# ATMEGA2560.net
KiCad netlist of a schematic drawn in Altium Designer
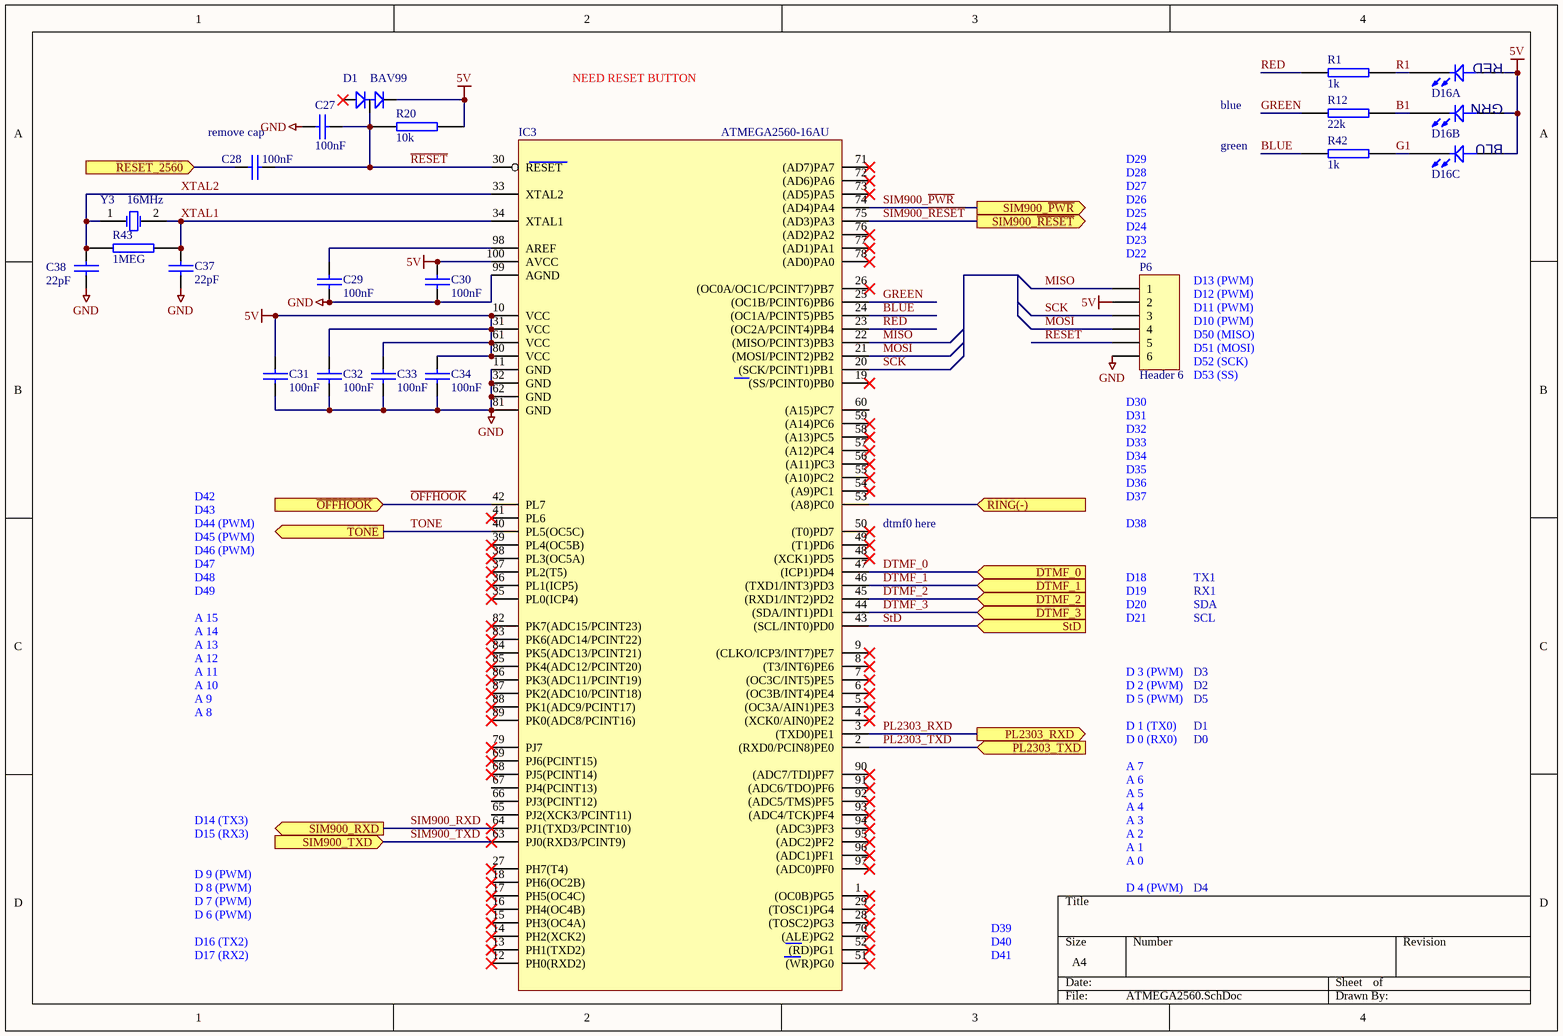
[diagram p0: ATMEGA2560.SchDoc]

(export (version "E")
  (design (tool "Eeschema 10.0.6"))
  (components
    (comp (ref "C27")
      (value "100nF")
      (footprint "CAP (3D) - 0603")
      (description "CAPACITOR SMD 0603")
      (fields (field (name "MOUSER PART NO.") "81-GCM188R71C104KA7D") (field (name "MANUFACTURER") "Murata"))
      (libsource (lib "NASCO Capacitors") (part "CAP SMD 0603 100nF"))
    )
    (comp (ref "C28")
      (value "100nF")
      (footprint "CAP (3D) - 0603")
      (description "CAPACITOR SMD 0603")
      (fields (field (name "MOUSER PART NO.") "81-GCM188R71C104KA7D") (field (name "MANUFACTURER") "Murata"))
      (libsource (lib "NASCO Capacitors") (part "CAP SMD 0603 100nF"))
    )
    (comp (ref "C29")
      (value "100nF")
      (footprint "CAP (3D) - 0603")
      (description "CAPACITOR SMD 0603")
      (fields (field (name "MOUSER PART NO.") "81-GCM188R71C104KA7D") (field (name "MANUFACTURER") "Murata"))
      (libsource (lib "NASCO Capacitors") (part "CAP SMD 0603 100nF"))
    )
    (comp (ref "C30")
      (value "100nF")
      (footprint "CAP (3D) - 0603")
      (description "CAPACITOR SMD 0603")
      (fields (field (name "MOUSER PART NO.") "81-GCM188R71C104KA7D") (field (name "MANUFACTURER") "Murata"))
      (libsource (lib "NASCO Capacitors") (part "CAP SMD 0603 100nF"))
    )
    (comp (ref "C31")
      (value "100nF")
      (footprint "CAP (3D) - 0603")
      (description "CAPACITOR SMD 0603")
      (fields (field (name "MOUSER PART NO.") "81-GCM188R71C104KA7D") (field (name "MANUFACTURER") "Murata"))
      (libsource (lib "NASCO Capacitors") (part "CAP SMD 0603 100nF"))
    )
    (comp (ref "C32")
      (value "100nF")
      (footprint "CAP (3D) - 0603")
      (description "CAPACITOR SMD 0603")
      (fields (field (name "MOUSER PART NO.") "81-GCM188R71C104KA7D") (field (name "MANUFACTURER") "Murata"))
      (libsource (lib "NASCO Capacitors") (part "CAP SMD 0603 100nF"))
    )
    (comp (ref "C33")
      (value "100nF")
      (footprint "CAP (3D) - 0603")
      (description "CAPACITOR SMD 0603")
      (fields (field (name "MOUSER PART NO.") "81-GCM188R71C104KA7D") (field (name "MANUFACTURER") "Murata"))
      (libsource (lib "NASCO Capacitors") (part "CAP SMD 0603 100nF"))
    )
    (comp (ref "C34")
      (value "100nF")
      (footprint "CAP (3D) - 0603")
      (description "CAPACITOR SMD 0603")
      (fields (field (name "MOUSER PART NO.") "81-GCM188R71C104KA7D") (field (name "MANUFACTURER") "Murata"))
      (libsource (lib "NASCO Capacitors") (part "CAP SMD 0603 100nF"))
    )
    (comp (ref "C37")
      (value "22pF")
      (footprint "CAP (3D) - 0603")
      (description "CAPACITOR SMD 0603")
      (fields
        (field (name "MANUFACTURER") "Vishay")
        (field (name "MANUFACTURER PART NO.") "VJ0603A220JXACW1BC")
      )
      (libsource (lib "NASCO Capacitors") (part "CAP SMD 0603 1nF"))
    )
    (comp (ref "C38")
      (value "22pF")
      (footprint "CAP (3D) - 0603")
      (description "CAPACITOR SMD 0603")
      (fields
        (field (name "MANUFACTURER") "Vishay")
        (field (name "MANUFACTURER PART NO.") "VJ0603A220JXACW1BC")
      )
      (libsource (lib "NASCO Capacitors") (part "CAP SMD 0603 1nF"))
    )
    (comp (ref "D1")
      (value "BAV99")
      (footprint "SOT23-3L")
      (description "DUAL DIODE, BAV99")
      (fields
        (field (name "MOUSER PART NO.") "771-BAV99/T3")
        (field (name "MANUFACTURER") "FAIRCHILD SEMICONDUCTOR")
      )
      (libsource (lib "NASCO") (part "BAV99"))
    )
    (comp (ref "D16")
      (value "RGB 5mm")
      (footprint "LED(3D) 5MM RIGHT ANGLE (RGB) - COMMON ANODE")
      (libsource (lib "NASCO") (part "RGB_5mm"))
    )
    (comp (ref "IC3")
      (value "ATMEGA2560-16AU")
      (footprint "TQFP100")
      (fields
        (field (name "MANUFACTURER") "Atmel")
        (field (name "MANUFACTURER PART NO.") "ATmega2560-16AU")
        (field (name "MOUSER PART NO.") "556-ATMEGA2560-16AU")
      )
      (libsource (lib "NASCO") (part "ATMEGA25602560-16AU"))
    )
    (comp (ref "P6")
      (value "Header 6")
      (footprint "HDR2X3 (3D)")
      (description "Header, 6-Pin")
      (libsource (lib "Miscellaneous Connectors") (part "Header 6"))
    )
    (comp (ref "R1")
      (value "1k")
      (footprint "RES (3D) - 0603")
      (description "RESISTOR SMD 0603")
      (fields (field (name "MOUSER PART NO.") "652-CR0603-JW-102ELF") (field (name "MANUFACTURER") "Bourns"))
      (libsource (lib "NASCO Resistors") (part "RES SMD 0603 10k"))
    )
    (comp (ref "R12")
      (value "22k")
      (footprint "RES (3D) - 0603")
      (description "RESISTOR SMD 0603")
      (fields (field (name "MOUSER PART NO.") "652-CR0603FX-4223ELF") (field (name "MANUFACTURER") "Bourns"))
      (libsource (lib "NASCO Resistors") (part "RES SMD 0603 10k"))
    )
    (comp (ref "R20")
      (value "10k")
      (footprint "RES (3D) - 0603")
      (description "RESISTOR SMD 0603 10k")
      (fields (field (name "MOUSER PART NO.") "652-CR0603FX-1002ELF") (field (name "MANUFACTURER") "Bourns"))
      (libsource (lib "NASCO Resistors") (part "RES SMD 0603 10k"))
    )
    (comp (ref "R42")
      (value "1k")
      (footprint "RES (3D) - 0603")
      (description "RESISTOR SMD 0603")
      (fields (field (name "MOUSER PART NO.") "652-CR0603-JW-102ELF") (field (name "MANUFACTURER") "Bourns"))
      (libsource (lib "NASCO Resistors") (part "RES SMD 0603 10k"))
    )
    (comp (ref "R43")
      (value "1MEG")
      (footprint "RES (3D) - 0603")
      (description "RESISTOR SMD 0603 0R")
      (fields
        (field (name "MANUFACTURER") "Bourns")
        (field (name "MANUFACTURER PART NO.") "CR0603-FX-1004ELF")
      )
      (libsource (lib "NASCO Resistors") (part "RES SMD 0603 0R"))
    )
    (comp (ref "Y3")
      (value "16MHz")
      (footprint "HC49/4H_SMX")
      (description "Crystal Oscillator")
      (fields (field (name "MOUSER PART NO.") "520-CSM1600-20-X") (field (name "MANUFACTURER") "ECS"))
      (libsource (lib "Miscellaneous Devices") (part "XTAL"))
    )
  )
  (nets
    (net (code "1") (name "/B1") (class "Default")
      (node (ref "D16") (pin "4") (pinfunction "K_4") (pintype "passive"))
      (node (ref "R12") (pin "2") (pinfunction "2_2") (pintype "passive"))
    )
    (net (code "2") (name "/BLUE") (class "Default")
      (node (ref "IC3") (pin "24") (pinfunction "(OC1A/PCINT5)PB5_24") (pintype "passive"))
      (node (ref "R42") (pin "1") (pinfunction "1_1") (pintype "passive"))
    )
    (net (code "3") (name "/DTMF_0") (class "Default")
      (node (ref "IC3") (pin "47") (pinfunction "(ICP1)PD4_47") (pintype "passive"))
    )
    (net (code "4") (name "/DTMF_1") (class "Default")
      (node (ref "IC3") (pin "46") (pinfunction "(TXD1/INT3)PD3_46") (pintype "passive"))
    )
    (net (code "5") (name "/DTMF_2") (class "Default")
      (node (ref "IC3") (pin "45") (pinfunction "(RXD1/INT2)PD2_45") (pintype "passive"))
    )
    (net (code "6") (name "/DTMF_3") (class "Default")
      (node (ref "IC3") (pin "44") (pinfunction "(SDA/INT1)PD1_44") (pintype "passive"))
    )
    (net (code "7") (name "/G1") (class "Default")
      (node (ref "D16") (pin "3") (pinfunction "K_3") (pintype "passive"))
      (node (ref "R42") (pin "2") (pinfunction "2_2") (pintype "passive"))
    )
    (net (code "8") (name "/GREEN") (class "Default")
      (node (ref "IC3") (pin "25") (pinfunction "(OC1B/PCINT6)PB6_25") (pintype "passive"))
      (node (ref "R12") (pin "1") (pinfunction "1_1") (pintype "passive"))
    )
    (net (code "9") (name "/MISO") (class "Default")
      (node (ref "IC3") (pin "22") (pinfunction "(MISO/PCINT3)PB3_22") (pintype "passive"))
      (node (ref "P6") (pin "1") (pinfunction "1_1") (pintype "passive"))
    )
    (net (code "10") (name "/MOSI") (class "Default")
      (node (ref "IC3") (pin "21") (pinfunction "(MOSI/PCINT2)PB2_21") (pintype "passive"))
      (node (ref "P6") (pin "4") (pinfunction "4_4") (pintype "passive"))
    )
    (net (code "11") (name "/PL2303_RXD") (class "Default")
      (node (ref "IC3") (pin "3") (pinfunction "(TXD0)PE1_3") (pintype "passive"))
    )
    (net (code "12") (name "/PL2303_TXD") (class "Default")
      (node (ref "IC3") (pin "2") (pinfunction "(RXD0/PCIN8)PE0_2") (pintype "passive"))
    )
    (net (code "13") (name "/R1") (class "Default")
      (node (ref "D16") (pin "1") (pinfunction "K_1") (pintype "passive"))
      (node (ref "R1") (pin "2") (pinfunction "2_2") (pintype "passive"))
    )
    (net (code "14") (name "/RED") (class "Default")
      (node (ref "IC3") (pin "23") (pinfunction "(OC2A/PCINT4)PB4_23") (pintype "passive"))
      (node (ref "R1") (pin "1") (pinfunction "1_1") (pintype "passive"))
    )
    (net (code "15") (name "/RESET_2560") (class "Default")
      (node (ref "C28") (pin "1") (pinfunction "1_1") (pintype "passive"))
    )
    (net (code "16") (name "/RING(-)") (class "Default")
      (node (ref "IC3") (pin "53") (pinfunction "(A8)PC0_53") (pintype "passive"))
    )
    (net (code "17") (name "/SCK") (class "Default")
      (node (ref "IC3") (pin "20") (pinfunction "(SCK/PCINT1)PB1_20") (pintype "passive"))
      (node (ref "P6") (pin "3") (pinfunction "3_3") (pintype "passive"))
    )
    (net (code "18") (name "/SIM900_RXD") (class "Default")
      (node (ref "IC3") (pin "64") (pinfunction "PJ1(TXD3/PCINT10)_64") (pintype "passive+no_connect"))
    )
    (net (code "19") (name "/SIM900_TXD") (class "Default")
      (node (ref "IC3") (pin "63") (pinfunction "PJ0(RXD3/PCINT9)_63") (pintype "passive+no_connect"))
    )
    (net (code "20") (name "/SIM900_~{PWR}") (class "Default")
      (node (ref "IC3") (pin "74") (pinfunction "(AD4)PA4_74") (pintype "passive"))
    )
    (net (code "21") (name "/SIM900_~{RESET}") (class "Default")
      (node (ref "IC3") (pin "75") (pinfunction "(AD3)PA3_75") (pintype "passive"))
    )
    (net (code "22") (name "/StD") (class "Default")
      (node (ref "IC3") (pin "43") (pinfunction "(SCL/INT0)PD0_43") (pintype "passive"))
    )
    (net (code "23") (name "/TONE") (class "Default")
      (node (ref "IC3") (pin "40") (pinfunction "PL5(OC5C)_40") (pintype "passive"))
    )
    (net (code "24") (name "/XTAL1") (class "Default")
      (node (ref "C37") (pin "1") (pinfunction "1_1") (pintype "passive"))
      (node (ref "IC3") (pin "34") (pinfunction "XTAL1_34") (pintype "passive"))
      (node (ref "R43") (pin "2") (pinfunction "2_2") (pintype "passive"))
      (node (ref "Y3") (pin "2") (pinfunction "OSC2_2") (pintype "passive"))
    )
    (net (code "25") (name "/XTAL2") (class "Default")
      (node (ref "C38") (pin "1") (pinfunction "1_1") (pintype "passive"))
      (node (ref "IC3") (pin "33") (pinfunction "XTAL2_33") (pintype "passive"))
      (node (ref "R43") (pin "1") (pinfunction "1_1") (pintype "passive"))
      (node (ref "Y3") (pin "1") (pinfunction "OSC1_1") (pintype "passive"))
    )
    (net (code "26") (name "/~{OFFHOOK}") (class "Default")
      (node (ref "IC3") (pin "42") (pinfunction "PL7_42") (pintype "passive"))
    )
    (net (code "27") (name "/~{RESET}") (class "Default")
      (node (ref "C27") (pin "2") (pinfunction "2_2") (pintype "passive"))
      (node (ref "C28") (pin "2") (pinfunction "2_2") (pintype "passive"))
      (node (ref "D1") (pin "3") (pinfunction "C1/A2_3") (pintype "passive"))
      (node (ref "IC3") (pin "30") (pinfunction "RESET_30") (pintype "passive"))
      (node (ref "P6") (pin "5") (pinfunction "5_5") (pintype "passive"))
      (node (ref "R20") (pin "1") (pinfunction "1_1") (pintype "passive"))
    )
    (net (code "28") (name "5V") (class "Default")
      (node (ref "C30") (pin "1") (pinfunction "1_1") (pintype "passive"))
      (node (ref "C31") (pin "1") (pinfunction "1_1") (pintype "passive"))
      (node (ref "C32") (pin "1") (pinfunction "1_1") (pintype "passive"))
      (node (ref "C33") (pin "1") (pinfunction "1_1") (pintype "passive"))
      (node (ref "C34") (pin "1") (pinfunction "1_1") (pintype "passive"))
      (node (ref "D1") (pin "2") (pinfunction "C2_2") (pintype "passive"))
      (node (ref "D16") (pin "2") (pinfunction "A_2") (pintype "passive"))
      (node (ref "IC3") (pin "10") (pinfunction "VCC_10") (pintype "passive"))
      (node (ref "IC3") (pin "100") (pinfunction "AVCC_100") (pintype "passive"))
      (node (ref "IC3") (pin "31") (pinfunction "VCC_31") (pintype "passive"))
      (node (ref "IC3") (pin "61") (pinfunction "VCC_61") (pintype "passive"))
      (node (ref "IC3") (pin "80") (pinfunction "VCC_80") (pintype "passive"))
      (node (ref "P6") (pin "2") (pinfunction "2_2") (pintype "passive"))
      (node (ref "R20") (pin "2") (pinfunction "2_2") (pintype "passive"))
    )
    (net (code "29") (name "GND") (class "Default")
      (node (ref "C27") (pin "1") (pinfunction "1_1") (pintype "passive"))
      (node (ref "C29") (pin "2") (pinfunction "2_2") (pintype "passive"))
      (node (ref "C30") (pin "2") (pinfunction "2_2") (pintype "passive"))
      (node (ref "C31") (pin "2") (pinfunction "2_2") (pintype "passive"))
      (node (ref "C32") (pin "2") (pinfunction "2_2") (pintype "passive"))
      (node (ref "C33") (pin "2") (pinfunction "2_2") (pintype "passive"))
      (node (ref "C34") (pin "2") (pinfunction "2_2") (pintype "passive"))
      (node (ref "C37") (pin "2") (pinfunction "2_2") (pintype "passive"))
      (node (ref "C38") (pin "2") (pinfunction "2_2") (pintype "passive"))
      (node (ref "IC3") (pin "11") (pinfunction "GND_11") (pintype "passive"))
      (node (ref "IC3") (pin "32") (pinfunction "GND_32") (pintype "passive"))
      (node (ref "IC3") (pin "62") (pinfunction "GND_62") (pintype "passive"))
      (node (ref "IC3") (pin "81") (pinfunction "GND_81") (pintype "passive"))
      (node (ref "IC3") (pin "99") (pinfunction "AGND_99") (pintype "passive"))
      (node (ref "P6") (pin "6") (pinfunction "6_6") (pintype "passive"))
    )
    (net (code "30") (name "Net-(IC3-AREF)") (class "Default")
      (node (ref "C29") (pin "1") (pinfunction "1_1") (pintype "passive"))
      (node (ref "IC3") (pin "98") (pinfunction "AREF_98") (pintype "passive"))
    )
    (net (code "31") (name "unconnected-(D1-A1-Pad1)") (class "Default")
      (node (ref "D1") (pin "1") (pinfunction "A1_1") (pintype "passive+no_connect"))
    )
    (net (code "32") (name "unconnected-(IC3-(A9)PC1-Pad54)") (class "Default")
      (node (ref "IC3") (pin "54") (pinfunction "(A9)PC1_54") (pintype "passive+no_connect"))
    )
    (net (code "33") (name "unconnected-(IC3-(A10)PC2-Pad55)") (class "Default")
      (node (ref "IC3") (pin "55") (pinfunction "(A10)PC2_55") (pintype "passive+no_connect"))
    )
    (net (code "34") (name "unconnected-(IC3-(A11)PC3-Pad56)") (class "Default")
      (node (ref "IC3") (pin "56") (pinfunction "(A11)PC3_56") (pintype "passive+no_connect"))
    )
    (net (code "35") (name "unconnected-(IC3-(A12)PC4-Pad57)") (class "Default")
      (node (ref "IC3") (pin "57") (pinfunction "(A12)PC4_57") (pintype "passive+no_connect"))
    )
    (net (code "36") (name "unconnected-(IC3-(A13)PC5-Pad58)") (class "Default")
      (node (ref "IC3") (pin "58") (pinfunction "(A13)PC5_58") (pintype "passive+no_connect"))
    )
    (net (code "37") (name "unconnected-(IC3-(A14)PC6-Pad59)") (class "Default")
      (node (ref "IC3") (pin "59") (pinfunction "(A14)PC6_59") (pintype "passive+no_connect"))
    )
    (net (code "38") (name "unconnected-(IC3-(A15)PC7-Pad60)") (class "Default")
      (node (ref "IC3") (pin "60") (pinfunction "(A15)PC7_60") (pintype "passive"))
    )
    (net (code "39") (name "unconnected-(IC3-(AD0)PA0-Pad78)") (class "Default")
      (node (ref "IC3") (pin "78") (pinfunction "(AD0)PA0_78") (pintype "passive+no_connect"))
    )
    (net (code "40") (name "unconnected-(IC3-(AD1)PA1-Pad77)") (class "Default")
      (node (ref "IC3") (pin "77") (pinfunction "(AD1)PA1_77") (pintype "passive+no_connect"))
    )
    (net (code "41") (name "unconnected-(IC3-(AD2)PA2-Pad76)") (class "Default")
      (node (ref "IC3") (pin "76") (pinfunction "(AD2)PA2_76") (pintype "passive+no_connect"))
    )
    (net (code "42") (name "unconnected-(IC3-(AD5)PA5-Pad73)") (class "Default")
      (node (ref "IC3") (pin "73") (pinfunction "(AD5)PA5_73") (pintype "passive+no_connect"))
    )
    (net (code "43") (name "unconnected-(IC3-(AD6)PA6-Pad72)") (class "Default")
      (node (ref "IC3") (pin "72") (pinfunction "(AD6)PA6_72") (pintype "passive+no_connect"))
    )
    (net (code "44") (name "unconnected-(IC3-(AD7)PA7-Pad71)") (class "Default")
      (node (ref "IC3") (pin "71") (pinfunction "(AD7)PA7_71") (pintype "passive+no_connect"))
    )
    (net (code "45") (name "unconnected-(IC3-(ADC0)PF0-Pad97)") (class "Default")
      (node (ref "IC3") (pin "97") (pinfunction "(ADC0)PF0_97") (pintype "passive+no_connect"))
    )
    (net (code "46") (name "unconnected-(IC3-(ADC1)PF1-Pad96)") (class "Default")
      (node (ref "IC3") (pin "96") (pinfunction "(ADC1)PF1_96") (pintype "passive+no_connect"))
    )
    (net (code "47") (name "unconnected-(IC3-(ADC2)PF2-Pad95)") (class "Default")
      (node (ref "IC3") (pin "95") (pinfunction "(ADC2)PF2_95") (pintype "passive+no_connect"))
    )
    (net (code "48") (name "unconnected-(IC3-(ADC3)PF3-Pad94)") (class "Default")
      (node (ref "IC3") (pin "94") (pinfunction "(ADC3)PF3_94") (pintype "passive+no_connect"))
    )
    (net (code "49") (name "unconnected-(IC3-(ADC4{slash}TCK)PF4-Pad93)") (class "Default")
      (node (ref "IC3") (pin "93") (pinfunction "(ADC4/TCK)PF4_93") (pintype "passive+no_connect"))
    )
    (net (code "50") (name "unconnected-(IC3-(ADC5{slash}TMS)PF5-Pad92)") (class "Default")
      (node (ref "IC3") (pin "92") (pinfunction "(ADC5/TMS)PF5_92") (pintype "passive+no_connect"))
    )
    (net (code "51") (name "unconnected-(IC3-(ADC6{slash}TDO)PF6-Pad91)") (class "Default")
      (node (ref "IC3") (pin "91") (pinfunction "(ADC6/TDO)PF6_91") (pintype "passive+no_connect"))
    )
    (net (code "52") (name "unconnected-(IC3-(ADC7{slash}TDI)PF7-Pad90)") (class "Default")
      (node (ref "IC3") (pin "90") (pinfunction "(ADC7/TDI)PF7_90") (pintype "passive+no_connect"))
    )
    (net (code "53") (name "unconnected-(IC3-(ALE)PG2-Pad70)") (class "Default")
      (node (ref "IC3") (pin "70") (pinfunction "(ALE)PG2_70") (pintype "passive+no_connect"))
    )
    (net (code "54") (name "unconnected-(IC3-(CLKO{slash}ICP3{slash}INT7)PE7-Pad9)") (class "Default")
      (node (ref "IC3") (pin "9") (pinfunction "(CLKO/ICP3/INT7)PE7_9") (pintype "passive+no_connect"))
    )
    (net (code "55") (name "unconnected-(IC3-(OC0A{slash}OC1C{slash}PCINT7)PB7-Pad26)") (class "Default")
      (node (ref "IC3") (pin "26") (pinfunction "(OC0A/OC1C/PCINT7)PB7_26") (pintype "passive+no_connect"))
    )
    (net (code "56") (name "unconnected-(IC3-(OC0B)PG5-Pad1)") (class "Default")
      (node (ref "IC3") (pin "1") (pinfunction "(OC0B)PG5_1") (pintype "passive+no_connect"))
    )
    (net (code "57") (name "unconnected-(IC3-(OC3A{slash}AIN1)PE3-Pad5)") (class "Default")
      (node (ref "IC3") (pin "5") (pinfunction "(OC3A/AIN1)PE3_5") (pintype "passive+no_connect"))
    )
    (net (code "58") (name "unconnected-(IC3-(OC3B{slash}INT4)PE4-Pad6)") (class "Default")
      (node (ref "IC3") (pin "6") (pinfunction "(OC3B/INT4)PE4_6") (pintype "passive+no_connect"))
    )
    (net (code "59") (name "unconnected-(IC3-(OC3C{slash}INT5)PE5-Pad7)") (class "Default")
      (node (ref "IC3") (pin "7") (pinfunction "(OC3C/INT5)PE5_7") (pintype "passive+no_connect"))
    )
    (net (code "60") (name "unconnected-(IC3-(RD)PG1-Pad52)") (class "Default")
      (node (ref "IC3") (pin "52") (pinfunction "(RD)PG1_52") (pintype "passive+no_connect"))
    )
    (net (code "61") (name "unconnected-(IC3-(SS{slash}PCINT0)PB0-Pad19)") (class "Default")
      (node (ref "IC3") (pin "19") (pinfunction "(SS/PCINT0)PB0_19") (pintype "passive+no_connect"))
    )
    (net (code "62") (name "unconnected-(IC3-(T0)PD7-Pad50)") (class "Default")
      (node (ref "IC3") (pin "50") (pinfunction "(T0)PD7_50") (pintype "passive+no_connect"))
    )
    (net (code "63") (name "unconnected-(IC3-(T1)PD6-Pad49)") (class "Default")
      (node (ref "IC3") (pin "49") (pinfunction "(T1)PD6_49") (pintype "passive+no_connect"))
    )
    (net (code "64") (name "unconnected-(IC3-(T3{slash}INT6)PE6-Pad8)") (class "Default")
      (node (ref "IC3") (pin "8") (pinfunction "(T3/INT6)PE6_8") (pintype "passive+no_connect"))
    )
    (net (code "65") (name "unconnected-(IC3-(TOSC1)PG4-Pad29)") (class "Default")
      (node (ref "IC3") (pin "29") (pinfunction "(TOSC1)PG4_29") (pintype "passive+no_connect"))
    )
    (net (code "66") (name "unconnected-(IC3-(TOSC2)PG3-Pad28)") (class "Default")
      (node (ref "IC3") (pin "28") (pinfunction "(TOSC2)PG3_28") (pintype "passive+no_connect"))
    )
    (net (code "67") (name "unconnected-(IC3-(WR)PG0-Pad51)") (class "Default")
      (node (ref "IC3") (pin "51") (pinfunction "(WR)PG0_51") (pintype "passive+no_connect"))
    )
    (net (code "68") (name "unconnected-(IC3-(XCK0{slash}AIN0)PE2-Pad4)") (class "Default")
      (node (ref "IC3") (pin "4") (pinfunction "(XCK0/AIN0)PE2_4") (pintype "passive+no_connect"))
    )
    (net (code "69") (name "unconnected-(IC3-(XCK1)PD5-Pad48)") (class "Default")
      (node (ref "IC3") (pin "48") (pinfunction "(XCK1)PD5_48") (pintype "passive+no_connect"))
    )
    (net (code "70") (name "unconnected-(IC3-PH0(RXD2)-Pad12)") (class "Default")
      (node (ref "IC3") (pin "12") (pinfunction "PH0(RXD2)_12") (pintype "passive+no_connect"))
    )
    (net (code "71") (name "unconnected-(IC3-PH1(TXD2)-Pad13)") (class "Default")
      (node (ref "IC3") (pin "13") (pinfunction "PH1(TXD2)_13") (pintype "passive+no_connect"))
    )
    (net (code "72") (name "unconnected-(IC3-PH2(XCK2)-Pad14)") (class "Default")
      (node (ref "IC3") (pin "14") (pinfunction "PH2(XCK2)_14") (pintype "passive+no_connect"))
    )
    (net (code "73") (name "unconnected-(IC3-PH3(OC4A)-Pad15)") (class "Default")
      (node (ref "IC3") (pin "15") (pinfunction "PH3(OC4A)_15") (pintype "passive+no_connect"))
    )
    (net (code "74") (name "unconnected-(IC3-PH4(OC4B)-Pad16)") (class "Default")
      (node (ref "IC3") (pin "16") (pinfunction "PH4(OC4B)_16") (pintype "passive+no_connect"))
    )
    (net (code "75") (name "unconnected-(IC3-PH5(OC4C)-Pad17)") (class "Default")
      (node (ref "IC3") (pin "17") (pinfunction "PH5(OC4C)_17") (pintype "passive+no_connect"))
    )
    (net (code "76") (name "unconnected-(IC3-PH6(OC2B)-Pad18)") (class "Default")
      (node (ref "IC3") (pin "18") (pinfunction "PH6(OC2B)_18") (pintype "passive+no_connect"))
    )
    (net (code "77") (name "unconnected-(IC3-PH7(T4)-Pad27)") (class "Default")
      (node (ref "IC3") (pin "27") (pinfunction "PH7(T4)_27") (pintype "passive+no_connect"))
    )
    (net (code "78") (name "unconnected-(IC3-PJ2(XCK3{slash}PCINT11)-Pad65)") (class "Default")
      (node (ref "IC3") (pin "65") (pinfunction "PJ2(XCK3/PCINT11)_65") (pintype "passive"))
    )
    (net (code "79") (name "unconnected-(IC3-PJ3(PCINT12)-Pad66)") (class "Default")
      (node (ref "IC3") (pin "66") (pinfunction "PJ3(PCINT12)_66") (pintype "passive"))
    )
    (net (code "80") (name "unconnected-(IC3-PJ4(PCINT13)-Pad67)") (class "Default")
      (node (ref "IC3") (pin "67") (pinfunction "PJ4(PCINT13)_67") (pintype "passive"))
    )
    (net (code "81") (name "unconnected-(IC3-PJ5(PCINT14)-Pad68)") (class "Default")
      (node (ref "IC3") (pin "68") (pinfunction "PJ5(PCINT14)_68") (pintype "passive+no_connect"))
    )
    (net (code "82") (name "unconnected-(IC3-PJ6(PCINT15)-Pad69)") (class "Default")
      (node (ref "IC3") (pin "69") (pinfunction "PJ6(PCINT15)_69") (pintype "passive+no_connect"))
    )
    (net (code "83") (name "unconnected-(IC3-PJ7-Pad79)") (class "Default")
      (node (ref "IC3") (pin "79") (pinfunction "PJ7_79") (pintype "passive+no_connect"))
    )
    (net (code "84") (name "unconnected-(IC3-PK0(ADC8{slash}PCINT16)-Pad89)") (class "Default")
      (node (ref "IC3") (pin "89") (pinfunction "PK0(ADC8/PCINT16)_89") (pintype "passive+no_connect"))
    )
    (net (code "85") (name "unconnected-(IC3-PK1(ADC9{slash}PCINT17)-Pad88)") (class "Default")
      (node (ref "IC3") (pin "88") (pinfunction "PK1(ADC9/PCINT17)_88") (pintype "passive+no_connect"))
    )
    (net (code "86") (name "unconnected-(IC3-PK2(ADC10{slash}PCINT18)-Pad87)") (class "Default")
      (node (ref "IC3") (pin "87") (pinfunction "PK2(ADC10/PCINT18)_87") (pintype "passive+no_connect"))
    )
    (net (code "87") (name "unconnected-(IC3-PK3(ADC11{slash}PCINT19)-Pad86)") (class "Default")
      (node (ref "IC3") (pin "86") (pinfunction "PK3(ADC11/PCINT19)_86") (pintype "passive+no_connect"))
    )
    (net (code "88") (name "unconnected-(IC3-PK4(ADC12{slash}PCINT20)-Pad85)") (class "Default")
      (node (ref "IC3") (pin "85") (pinfunction "PK4(ADC12/PCINT20)_85") (pintype "passive+no_connect"))
    )
    (net (code "89") (name "unconnected-(IC3-PK5(ADC13{slash}PCINT21)-Pad84)") (class "Default")
      (node (ref "IC3") (pin "84") (pinfunction "PK5(ADC13/PCINT21)_84") (pintype "passive+no_connect"))
    )
    (net (code "90") (name "unconnected-(IC3-PK6(ADC14{slash}PCINT22)-Pad83)") (class "Default")
      (node (ref "IC3") (pin "83") (pinfunction "PK6(ADC14/PCINT22)_83") (pintype "passive+no_connect"))
    )
    (net (code "91") (name "unconnected-(IC3-PK7(ADC15{slash}PCINT23)-Pad82)") (class "Default")
      (node (ref "IC3") (pin "82") (pinfunction "PK7(ADC15/PCINT23)_82") (pintype "passive+no_connect"))
    )
    (net (code "92") (name "unconnected-(IC3-PL0(ICP4)-Pad35)") (class "Default")
      (node (ref "IC3") (pin "35") (pinfunction "PL0(ICP4)_35") (pintype "passive+no_connect"))
    )
    (net (code "93") (name "unconnected-(IC3-PL1(ICP5)-Pad36)") (class "Default")
      (node (ref "IC3") (pin "36") (pinfunction "PL1(ICP5)_36") (pintype "passive+no_connect"))
    )
    (net (code "94") (name "unconnected-(IC3-PL2(T5)-Pad37)") (class "Default")
      (node (ref "IC3") (pin "37") (pinfunction "PL2(T5)_37") (pintype "passive+no_connect"))
    )
    (net (code "95") (name "unconnected-(IC3-PL3(OC5A)-Pad38)") (class "Default")
      (node (ref "IC3") (pin "38") (pinfunction "PL3(OC5A)_38") (pintype "passive+no_connect"))
    )
    (net (code "96") (name "unconnected-(IC3-PL4(OC5B)-Pad39)") (class "Default")
      (node (ref "IC3") (pin "39") (pinfunction "PL4(OC5B)_39") (pintype "passive+no_connect"))
    )
    (net (code "97") (name "unconnected-(IC3-PL6-Pad41)") (class "Default")
      (node (ref "IC3") (pin "41") (pinfunction "PL6_41") (pintype "passive+no_connect"))
    )
  )
)
